# MODELO_TRANSFORMADOR.net
KiCad netlist of a schematic drawn in Altium Designer
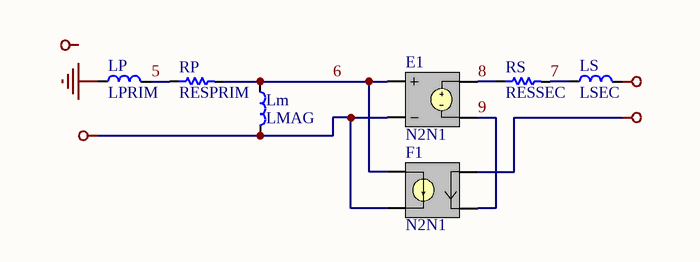
[diagram p0: MODELO TRANSFORMADOR.SCHDOC]

(export (version "E")
  (design (tool "Eeschema 10.0.6"))
  (components
    (comp (ref "E1")
      (value "ESRC")
      (description "Voltage Controlled Voltage Source")
      (fields (field (name "GAIN") "N2N1") (field (name "PUBLISHER") "Altium Limited"))
      (libsource (lib "Simulation Sources") (part "ESRC"))
    )
    (comp (ref "F1")
      (value "FSRC")
      (description "Current Controlled Current Source")
      (fields (field (name "GAIN") "N2N1") (field (name "PUBLISHER") "Altium Limited"))
      (libsource (lib "Simulation Sources") (part "FSRC"))
    )
    (comp (ref "Lm")
      (value "LMAG")
      (footprint "TOROIDE TN14-9-5")
      (description "Inductor")
      (fields (field (name "Comment") "Inductor2"))
      (libsource (lib "FEDE") (part "Inductor2"))
    )
    (comp (ref "LP")
      (value "LPRIM")
      (footprint "TOROIDE TN14-9-5")
      (description "Inductor")
      (fields (field (name "Comment") "Inductor2"))
      (libsource (lib "FEDE") (part "Inductor2"))
    )
    (comp (ref "LS")
      (value "LSEC")
      (footprint "TOROIDE TN14-9-5")
      (description "Inductor")
      (fields (field (name "Comment") "Inductor2"))
      (libsource (lib "FEDE") (part "Inductor2"))
    )
    (comp (ref "RP")
      (value "RESPRIM")
      (footprint "0805")
      (description "Resistor")
      (fields (field (name "POWER") "0.25W") (field (name "Comment") "Res"))
      (libsource (lib "FEDE") (part "Res"))
    )
    (comp (ref "RS")
      (value "RESSEC")
      (footprint "0805")
      (description "Resistor")
      (fields (field (name "POWER") "0.25W") (field (name "Comment") "Res"))
      (libsource (lib "FEDE") (part "Res"))
    )
  )
  (nets
    (net (code "1") (name "/5") (class "Default")
      (node (ref "LP") (pin "2") (pinfunction "2_2") (pintype "passive"))
      (node (ref "RP") (pin "1") (pinfunction "1_1") (pintype "passive"))
    )
    (net (code "2") (name "/6") (class "Default")
      (node (ref "E1") (pin "1") (pinfunction "NC+_1") (pintype "passive"))
      (node (ref "F1") (pin "3") (pinfunction "N+_3") (pintype "passive"))
      (node (ref "Lm") (pin "1") (pinfunction "1_1") (pintype "passive"))
      (node (ref "RP") (pin "2") (pinfunction "2_2") (pintype "passive"))
    )
    (net (code "3") (name "/7") (class "Default")
      (node (ref "LS") (pin "1") (pinfunction "1_1") (pintype "passive"))
      (node (ref "RS") (pin "2") (pinfunction "2_2") (pintype "passive"))
    )
    (net (code "4") (name "/8") (class "Default")
      (node (ref "E1") (pin "3") (pinfunction "N+_3") (pintype "passive"))
      (node (ref "RS") (pin "1") (pinfunction "1_1") (pintype "passive"))
    )
    (net (code "5") (name "/9") (class "Default")
      (node (ref "E1") (pin "4") (pinfunction "N-_4") (pintype "passive"))
      (node (ref "F1") (pin "2") (pinfunction "NC-_2") (pintype "passive"))
    )
    (net (code "7") (name "2") (class "Default")
      (node (ref "E1") (pin "2") (pinfunction "NC-_2") (pintype "passive"))
      (node (ref "F1") (pin "4") (pinfunction "N-_4") (pintype "passive"))
      (node (ref "Lm") (pin "2") (pinfunction "2_2") (pintype "passive"))
    )
    (net (code "8") (name "3") (class "Default")
      (node (ref "LS") (pin "2") (pinfunction "2_2") (pintype "passive"))
    )
    (net (code "9") (name "4") (class "Default")
      (node (ref "F1") (pin "1") (pinfunction "NC+_1") (pintype "passive"))
    )
    (net (code "10") (name "GND") (class "Default")
      (node (ref "LP") (pin "1") (pinfunction "1_1") (pintype "passive"))
    )
  )
)
